# Slave1.net
KiCad netlist of a schematic drawn in Altium Designer
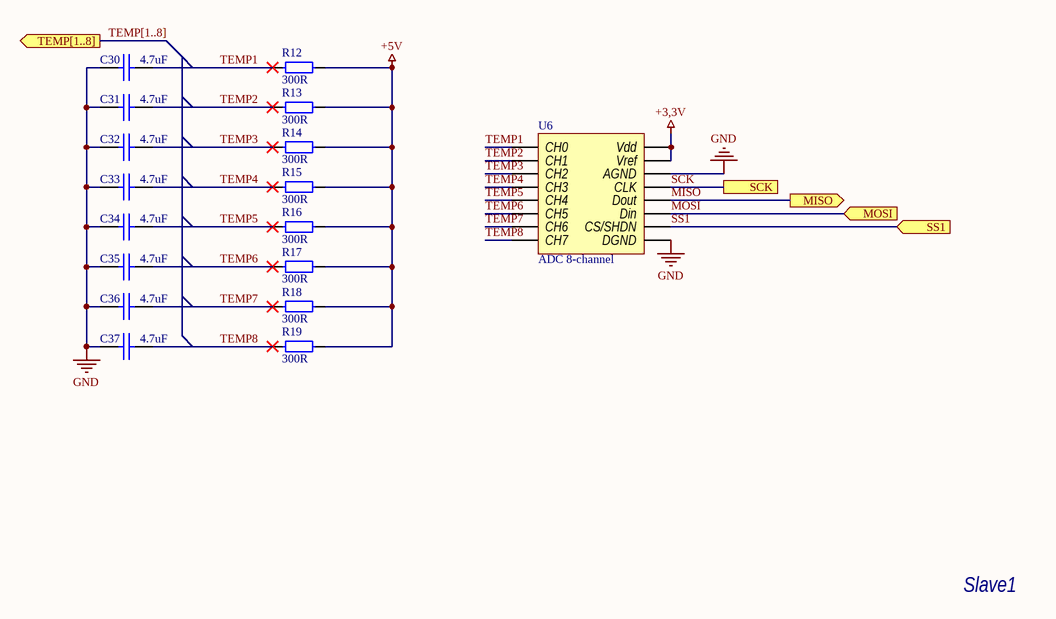
[diagram p0: Slave1.SchDoc]

(export (version "E")
  (design (tool "Eeschema 10.0.6"))
  (components
    (comp (ref "C30")
      (value "4.7uF")
      (footprint "0603 Capicator")
      (description "4.7uF X5R 25V 10% 0603")
      (fields
        (field (name "MANUFACTURER") "Murata Manufacturing")
        (field (name "PART NUMBER") "GRM188R61E475KE11D")
      )
      (libsource (lib "БУС") (part "Cap 4.7uF (0603)"))
    )
    (comp (ref "C31")
      (value "4.7uF")
      (footprint "0603 Capicator")
      (description "4.7uF X5R 25V 10% 0603")
      (fields
        (field (name "MANUFACTURER") "Murata Manufacturing")
        (field (name "PART NUMBER") "GRM188R61E475KE11D")
      )
      (libsource (lib "БУС") (part "Cap 4.7uF (0603)"))
    )
    (comp (ref "C32")
      (value "4.7uF")
      (footprint "0603 Capicator")
      (description "4.7uF X5R 25V 10% 0603")
      (fields
        (field (name "MANUFACTURER") "Murata Manufacturing")
        (field (name "PART NUMBER") "GRM188R61E475KE11D")
      )
      (libsource (lib "БУС") (part "Cap 4.7uF (0603)"))
    )
    (comp (ref "C33")
      (value "4.7uF")
      (footprint "0603 Capicator")
      (description "4.7uF X5R 25V 10% 0603")
      (fields
        (field (name "MANUFACTURER") "Murata Manufacturing")
        (field (name "PART NUMBER") "GRM188R61E475KE11D")
      )
      (libsource (lib "БУС") (part "Cap 4.7uF (0603)"))
    )
    (comp (ref "C34")
      (value "4.7uF")
      (footprint "0603 Capicator")
      (description "4.7uF X5R 25V 10% 0603")
      (fields
        (field (name "MANUFACTURER") "Murata Manufacturing")
        (field (name "PART NUMBER") "GRM188R61E475KE11D")
      )
      (libsource (lib "БУС") (part "Cap 4.7uF (0603)"))
    )
    (comp (ref "C35")
      (value "4.7uF")
      (footprint "0603 Capicator")
      (description "4.7uF X5R 25V 10% 0603")
      (fields
        (field (name "MANUFACTURER") "Murata Manufacturing")
        (field (name "PART NUMBER") "GRM188R61E475KE11D")
      )
      (libsource (lib "БУС") (part "Cap 4.7uF (0603)"))
    )
    (comp (ref "C36")
      (value "4.7uF")
      (footprint "0603 Capicator")
      (description "4.7uF X5R 25V 10% 0603")
      (fields
        (field (name "MANUFACTURER") "Murata Manufacturing")
        (field (name "PART NUMBER") "GRM188R61E475KE11D")
      )
      (libsource (lib "БУС") (part "Cap 4.7uF (0603)"))
    )
    (comp (ref "C37")
      (value "4.7uF")
      (footprint "0603 Capicator")
      (description "4.7uF X5R 25V 10% 0603")
      (fields
        (field (name "MANUFACTURER") "Murata Manufacturing")
        (field (name "PART NUMBER") "GRM188R61E475KE11D")
      )
      (libsource (lib "БУС") (part "Cap 4.7uF (0603)"))
    )
    (comp (ref "R12")
      (value "300R")
      (footprint "0603 Resistor")
      (description "0.1W 0603 300R, 1%")
      (fields (field (name "PART NUMBER") "RC0603FR-07360RL") (field (name "MANUFACTURER") "Taiwan"))
      (libsource (lib "БУС") (part "Res 300R (0603)"))
    )
    (comp (ref "R13")
      (value "300R")
      (footprint "0603 Resistor")
      (description "0.1W 0603 300R, 1%")
      (fields (field (name "PART NUMBER") "RC0603FR-07360RL") (field (name "MANUFACTURER") "Taiwan"))
      (libsource (lib "БУС") (part "Res 300R (0603)"))
    )
    (comp (ref "R14")
      (value "300R")
      (footprint "0603 Resistor")
      (description "0.1W 0603 300R, 1%")
      (fields (field (name "PART NUMBER") "RC0603FR-07360RL") (field (name "MANUFACTURER") "Taiwan"))
      (libsource (lib "БУС") (part "Res 300R (0603)"))
    )
    (comp (ref "R15")
      (value "300R")
      (footprint "0603 Resistor")
      (description "0.1W 0603 300R, 1%")
      (fields (field (name "PART NUMBER") "RC0603FR-07360RL") (field (name "MANUFACTURER") "Taiwan"))
      (libsource (lib "БУС") (part "Res 300R (0603)"))
    )
    (comp (ref "R16")
      (value "300R")
      (footprint "0603 Resistor")
      (description "0.1W 0603 300R, 1%")
      (fields (field (name "PART NUMBER") "RC0603FR-07360RL") (field (name "MANUFACTURER") "Taiwan"))
      (libsource (lib "БУС") (part "Res 300R (0603)"))
    )
    (comp (ref "R17")
      (value "300R")
      (footprint "0603 Resistor")
      (description "0.1W 0603 300R, 1%")
      (fields (field (name "PART NUMBER") "RC0603FR-07360RL") (field (name "MANUFACTURER") "Taiwan"))
      (libsource (lib "БУС") (part "Res 300R (0603)"))
    )
    (comp (ref "R18")
      (value "300R")
      (footprint "0603 Resistor")
      (description "0.1W 0603 300R, 1%")
      (fields (field (name "PART NUMBER") "RC0603FR-07360RL") (field (name "MANUFACTURER") "Taiwan"))
      (libsource (lib "БУС") (part "Res 300R (0603)"))
    )
    (comp (ref "R19")
      (value "300R")
      (footprint "0603 Resistor")
      (description "0.1W 0603 300R, 1%")
      (fields (field (name "PART NUMBER") "RC0603FR-07360RL") (field (name "MANUFACTURER") "Taiwan"))
      (libsource (lib "БУС") (part "Res 300R (0603)"))
    )
    (comp (ref "U6")
      (value "ADC 8-channel")
      (footprint "SOIC-16")
      (description "A/D converter with SPI serial interface")
      (fields (field (name "MANUFACTURER") "Microchip") (field (name "PART NUMBER") "MCP3008-I/SL"))
      (libsource (lib "БУС") (part "MCP3008-I/SL"))
    )
  )
  (nets
    (net (code "1") (name "+3,3V") (class "Default")
      (node (ref "U6") (pin "15") (pinfunction "Vref_15") (pintype "passive"))
      (node (ref "U6") (pin "16") (pinfunction "Vdd_16") (pintype "passive"))
    )
    (net (code "2") (name "+5V") (class "Default")
      (node (ref "R12") (pin "2") (pinfunction "2_2") (pintype "passive"))
      (node (ref "R13") (pin "2") (pinfunction "2_2") (pintype "passive"))
      (node (ref "R14") (pin "2") (pinfunction "2_2") (pintype "passive"))
      (node (ref "R15") (pin "2") (pinfunction "2_2") (pintype "passive"))
      (node (ref "R16") (pin "2") (pinfunction "2_2") (pintype "passive"))
      (node (ref "R17") (pin "2") (pinfunction "2_2") (pintype "passive"))
      (node (ref "R18") (pin "2") (pinfunction "2_2") (pintype "passive"))
      (node (ref "R19") (pin "2") (pinfunction "2_2") (pintype "passive"))
    )
    (net (code "3") (name "/MISO") (class "Default")
      (node (ref "U6") (pin "12") (pinfunction "Dout_12") (pintype "passive"))
    )
    (net (code "4") (name "/MOSI") (class "Default")
      (node (ref "U6") (pin "11") (pinfunction "Din_11") (pintype "passive"))
    )
    (net (code "5") (name "/SCK") (class "Default")
      (node (ref "U6") (pin "13") (pinfunction "CLK_13") (pintype "passive"))
    )
    (net (code "6") (name "/SS1") (class "Default")
      (node (ref "U6") (pin "10") (pinfunction "CS/SHDN_10") (pintype "passive"))
    )
    (net (code "7") (name "/TEMP1") (class "Default")
      (node (ref "C30") (pin "2") (pinfunction "2_2") (pintype "passive"))
      (node (ref "R12") (pin "1") (pinfunction "1_1") (pintype "passive"))
      (node (ref "U6") (pin "1") (pinfunction "CH0_1") (pintype "passive"))
    )
    (net (code "8") (name "/TEMP2") (class "Default")
      (node (ref "C31") (pin "2") (pinfunction "2_2") (pintype "passive"))
      (node (ref "R13") (pin "1") (pinfunction "1_1") (pintype "passive"))
      (node (ref "U6") (pin "2") (pinfunction "CH1_2") (pintype "passive"))
    )
    (net (code "9") (name "/TEMP3") (class "Default")
      (node (ref "C32") (pin "2") (pinfunction "2_2") (pintype "passive"))
      (node (ref "R14") (pin "1") (pinfunction "1_1") (pintype "passive"))
      (node (ref "U6") (pin "3") (pinfunction "CH2_3") (pintype "passive"))
    )
    (net (code "10") (name "/TEMP4") (class "Default")
      (node (ref "C33") (pin "2") (pinfunction "2_2") (pintype "passive"))
      (node (ref "R15") (pin "1") (pinfunction "1_1") (pintype "passive"))
      (node (ref "U6") (pin "4") (pinfunction "CH3_4") (pintype "passive"))
    )
    (net (code "11") (name "/TEMP5") (class "Default")
      (node (ref "C34") (pin "2") (pinfunction "2_2") (pintype "passive"))
      (node (ref "R16") (pin "1") (pinfunction "1_1") (pintype "passive"))
      (node (ref "U6") (pin "5") (pinfunction "CH4_5") (pintype "passive"))
    )
    (net (code "12") (name "/TEMP6") (class "Default")
      (node (ref "C35") (pin "2") (pinfunction "2_2") (pintype "passive"))
      (node (ref "R17") (pin "1") (pinfunction "1_1") (pintype "passive"))
      (node (ref "U6") (pin "6") (pinfunction "CH5_6") (pintype "passive"))
    )
    (net (code "13") (name "/TEMP7") (class "Default")
      (node (ref "C36") (pin "2") (pinfunction "2_2") (pintype "passive"))
      (node (ref "R18") (pin "1") (pinfunction "1_1") (pintype "passive"))
      (node (ref "U6") (pin "7") (pinfunction "CH6_7") (pintype "passive"))
    )
    (net (code "14") (name "/TEMP8") (class "Default")
      (node (ref "C37") (pin "2") (pinfunction "2_2") (pintype "passive"))
      (node (ref "R19") (pin "1") (pinfunction "1_1") (pintype "passive"))
      (node (ref "U6") (pin "8") (pinfunction "CH7_8") (pintype "passive"))
    )
    (net (code "16") (name "GND") (class "Default")
      (node (ref "C30") (pin "1") (pinfunction "1_1") (pintype "passive"))
      (node (ref "C31") (pin "1") (pinfunction "1_1") (pintype "passive"))
      (node (ref "C32") (pin "1") (pinfunction "1_1") (pintype "passive"))
      (node (ref "C33") (pin "1") (pinfunction "1_1") (pintype "passive"))
      (node (ref "C34") (pin "1") (pinfunction "1_1") (pintype "passive"))
      (node (ref "C35") (pin "1") (pinfunction "1_1") (pintype "passive"))
      (node (ref "C36") (pin "1") (pinfunction "1_1") (pintype "passive"))
      (node (ref "C37") (pin "1") (pinfunction "1_1") (pintype "passive"))
      (node (ref "U6") (pin "14") (pinfunction "AGND_14") (pintype "passive"))
      (node (ref "U6") (pin "9") (pinfunction "DGND_9") (pintype "passive"))
    )
  )
)
